# FmcConnector.net
KiCad netlist of a schematic drawn in Altium Designer
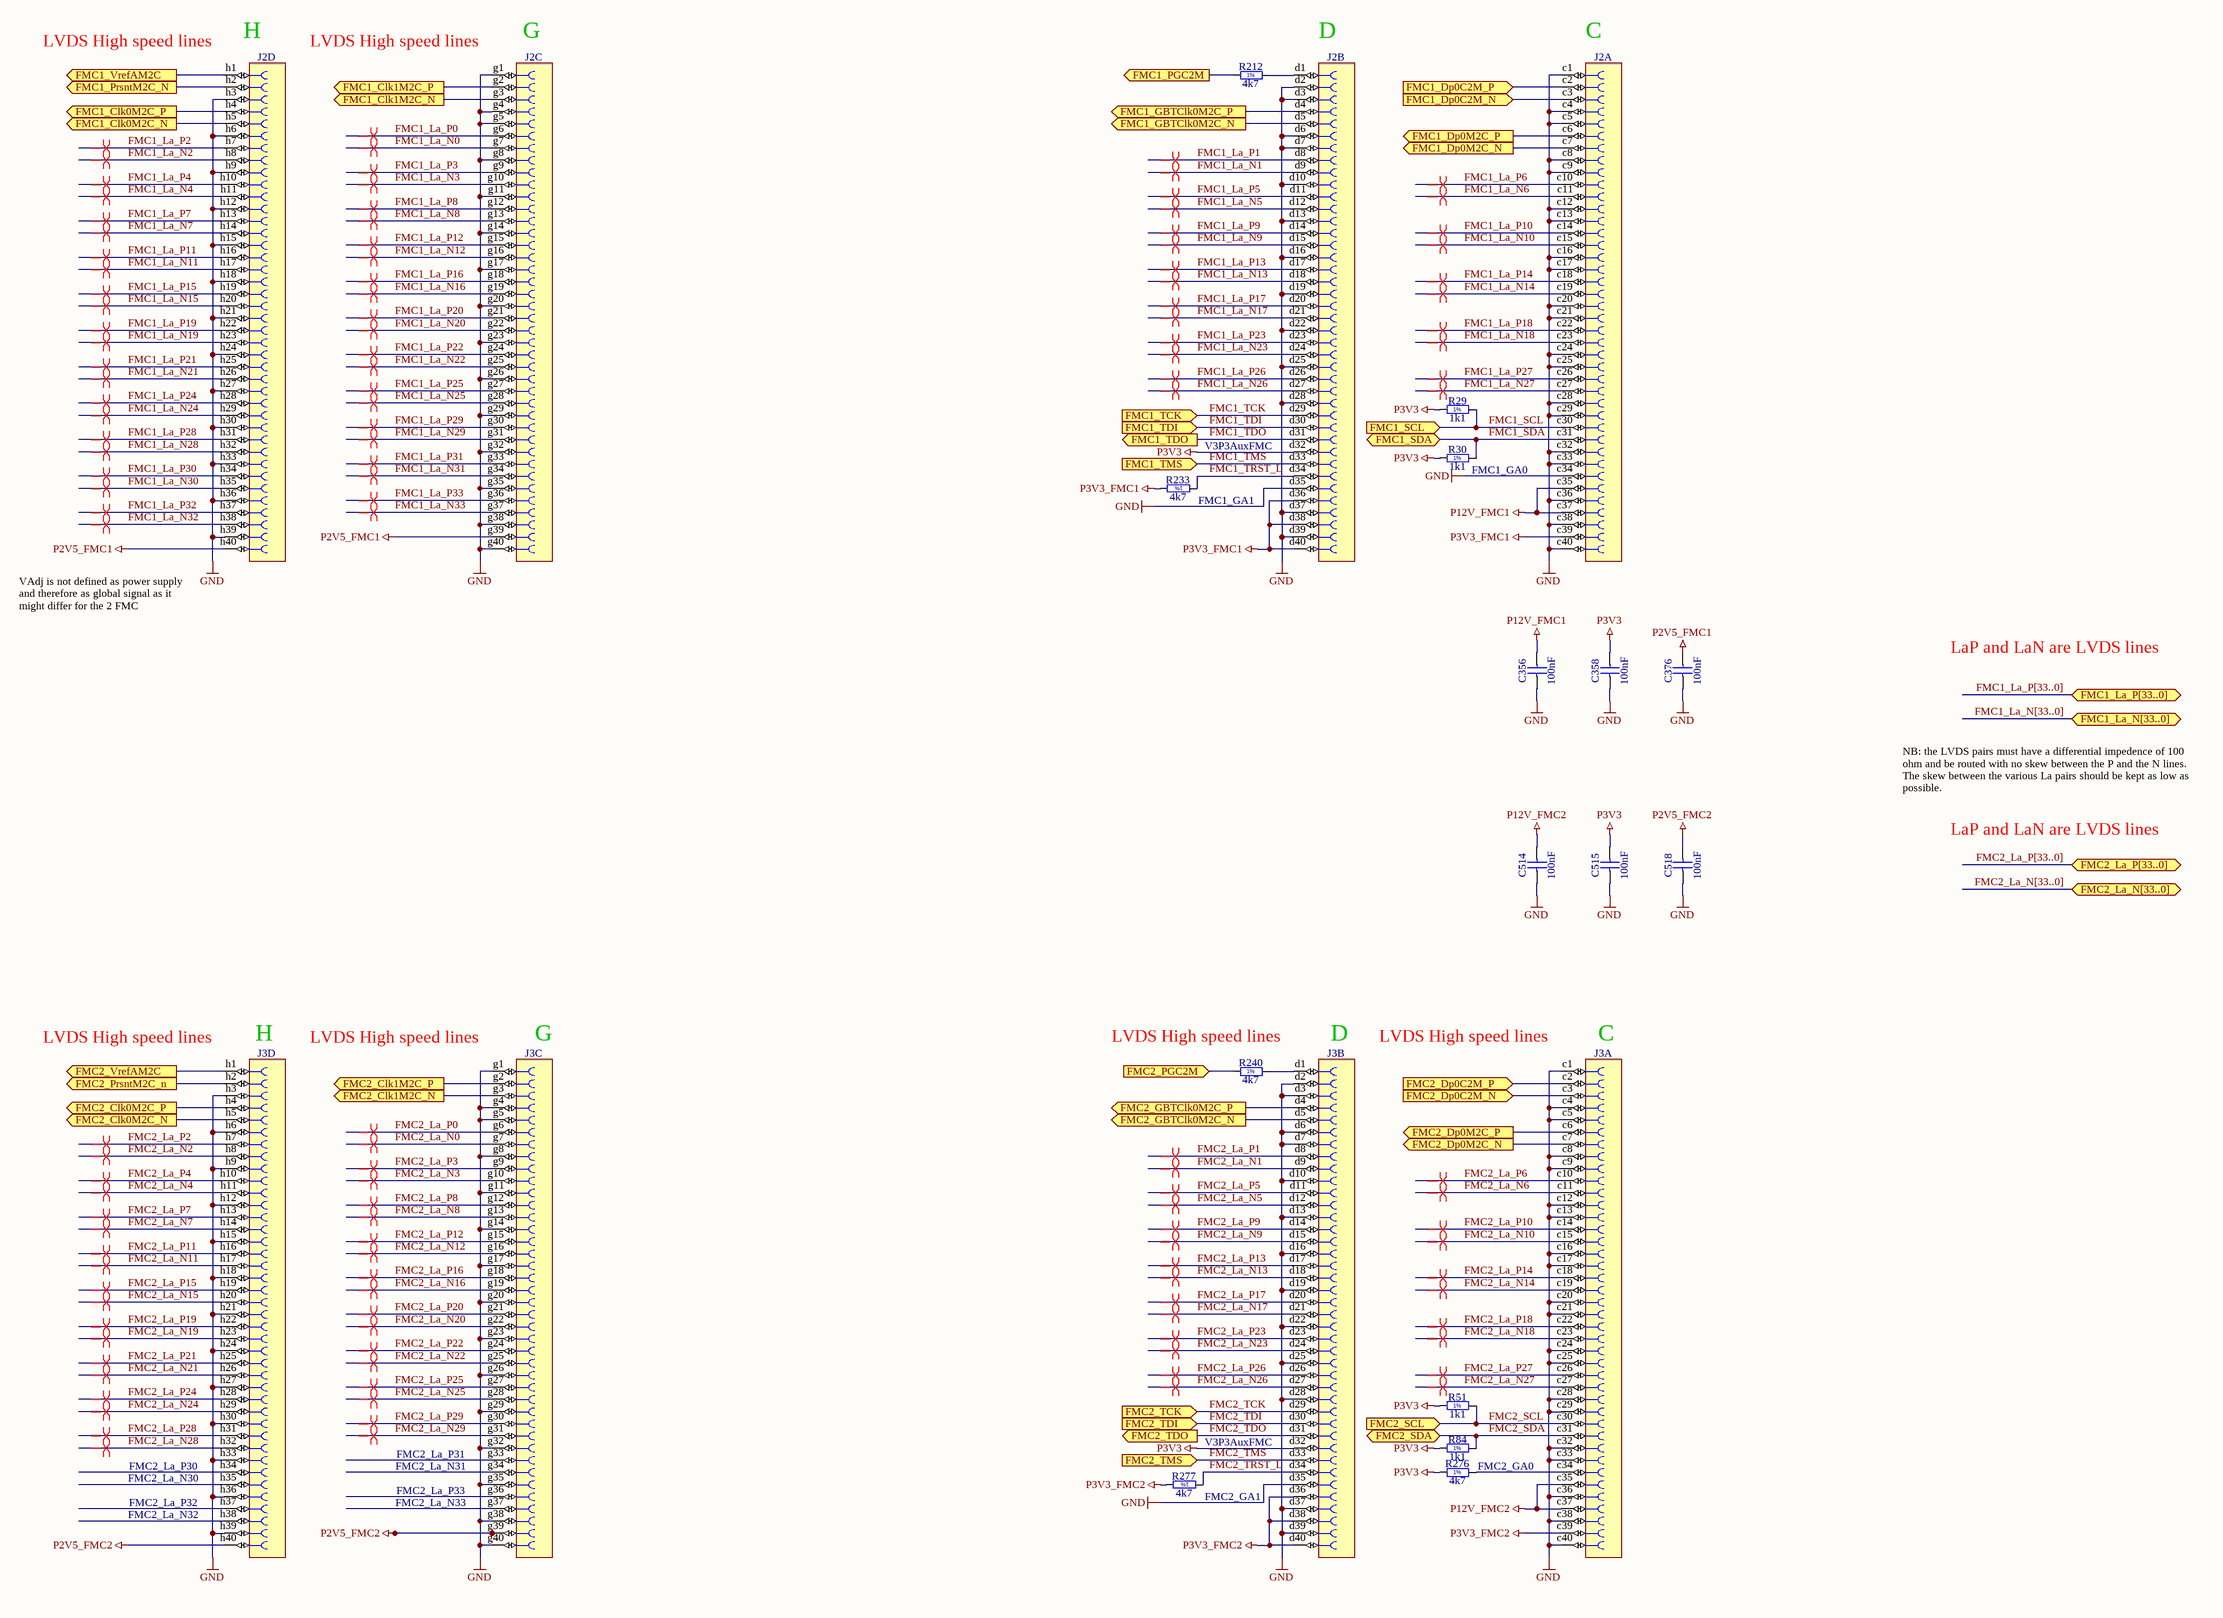
[diagram p0: FmcConnector.SchDoc]

(export (version "E")
  (design (tool "Eeschema 10.0.6"))
  (components
    (comp (ref "C356")
      (value "100nF")
      (footprint "CAPC1005X55N")
      (description "Non-polarised capacitor")
      (fields
        (field (name "PART NUMBER") "CC0402_100NF_16V_10%_X7R")
        (field (name "VOLTAGE") "16V")
        (field (name "AUTHOR") "CERN DEM JLC")
      )
      (libsource (lib "Capacitors") (part "Capacitor - non polarized"))
    )
    (comp (ref "C358")
      (value "100nF")
      (footprint "CAPC1005X55N")
      (description "Non-polarised capacitor")
      (fields
        (field (name "PART NUMBER") "CC0402_100NF_16V_10%_X7R")
        (field (name "VOLTAGE") "16V")
        (field (name "AUTHOR") "CERN DEM JLC")
      )
      (libsource (lib "Capacitors") (part "Capacitor - non polarized"))
    )
    (comp (ref "C376")
      (value "100nF")
      (footprint "CAPC1005X55N")
      (description "Non-polarised capacitor")
      (fields
        (field (name "PART NUMBER") "CC0402_100NF_16V_10%_X7R")
        (field (name "VOLTAGE") "16V")
        (field (name "AUTHOR") "CERN DEM JLC")
      )
      (libsource (lib "Capacitors") (part "Capacitor - non polarized"))
    )
    (comp (ref "C514")
      (value "100nF")
      (footprint "CAPC1005X55N")
      (description "Non-polarised capacitor")
      (fields
        (field (name "PART NUMBER") "CC0402_100NF_16V_10%_X7R")
        (field (name "VOLTAGE") "16V")
        (field (name "AUTHOR") "CERN DEM JLC")
      )
      (libsource (lib "Capacitors") (part "Capacitor - non polarized"))
    )
    (comp (ref "C515")
      (value "100nF")
      (footprint "CAPC1005X55N")
      (description "Non-polarised capacitor")
      (fields
        (field (name "PART NUMBER") "CC0402_100NF_16V_10%_X7R")
        (field (name "VOLTAGE") "16V")
        (field (name "AUTHOR") "CERN DEM JLC")
      )
      (libsource (lib "Capacitors") (part "Capacitor - non polarized"))
    )
    (comp (ref "C518")
      (value "100nF")
      (footprint "CAPC1005X55N")
      (description "Non-polarised capacitor")
      (fields
        (field (name "PART NUMBER") "CC0402_100NF_16V_10%_X7R")
        (field (name "VOLTAGE") "16V")
        (field (name "AUTHOR") "CERN DEM JLC")
      )
      (libsource (lib "Capacitors") (part "Capacitor - non polarized"))
    )
    (comp (ref "J2")
      (value "VITA 57")
      (footprint "SAMTEC_ASP-134603-01")
      (description "Connector VITA 57, 160 Female contacts in 4 row cdgh")
      (fields
        (field (name "PART NUMBER") "SAMTEC_ASP-134603-01")
        (field (name "MANUFACTURER") "SAMTEC")
        (field (name "AUTHOR") "CERN DEM JLC")
      )
      (libsource (lib "Connectors") (part "Connector VITA 57 160 Female (cdgh)"))
    )
    (comp (ref "J3")
      (value "VITA 57")
      (footprint "SAMTEC_ASP-134603-01")
      (description "Connector VITA 57, 160 Female contacts in 4 row cdgh")
      (fields
        (field (name "PART NUMBER") "SAMTEC_ASP-134603-01")
        (field (name "MANUFACTURER") "SAMTEC")
        (field (name "AUTHOR") "CERN DEM JLC")
      )
      (libsource (lib "Connectors") (part "Connector VITA 57 160 Female (cdgh)"))
    )
    (comp (ref "R29")
      (value "1k1")
      (footprint "RESC1608X55N")
      (description "Resistor - 1%")
      (fields
        (field (name "PART NUMBER") "R0603_1K1_1%_0.1W_100PPM")
        (field (name "POWER") "0.1W")
        (field (name "AUTHOR") "CERN DEM JLC")
      )
      (libsource (lib "Resistors") (part "Resistor - 1%"))
    )
    (comp (ref "R30")
      (value "1k1")
      (footprint "RESC1608X55N")
      (description "Resistor - 1%")
      (fields
        (field (name "PART NUMBER") "R0603_1K1_1%_0.1W_100PPM")
        (field (name "POWER") "0.1W")
        (field (name "AUTHOR") "CERN DEM JLC")
      )
      (libsource (lib "Resistors") (part "Resistor - 1%"))
    )
    (comp (ref "R51")
      (value "1k1")
      (footprint "RESC1608X55N")
      (description "Resistor - 1%")
      (fields
        (field (name "PART NUMBER") "R0603_1K1_1%_0.1W_100PPM")
        (field (name "POWER") "0.1W")
        (field (name "AUTHOR") "CERN DEM JLC")
      )
      (libsource (lib "Resistors") (part "Resistor - 1%"))
    )
    (comp (ref "R84")
      (value "1k1")
      (footprint "RESC1608X55N")
      (description "Resistor - 1%")
      (fields
        (field (name "PART NUMBER") "R0603_1K1_1%_0.1W_100PPM")
        (field (name "POWER") "0.1W")
        (field (name "AUTHOR") "CERN DEM JLC")
      )
      (libsource (lib "Resistors") (part "Resistor - 1%"))
    )
    (comp (ref "R212")
      (value "4k7")
      (footprint "RESC1608X55N")
      (description "Resistor - 1%")
      (fields
        (field (name "PART NUMBER") "R0603_4K7_1%_0.1W_100PPM")
        (field (name "POWER") "0.1W")
        (field (name "AUTHOR") "CERN DEM JLC")
      )
      (libsource (lib "Resistors") (part "Resistor - 1%"))
    )
    (comp (ref "R233")
      (value "4k7")
      (footprint "RESC1608X55N")
      (description "Resistor - 1%")
      (fields
        (field (name "PART NUMBER") "R0603_4K7_1%_0.1W_100PPM")
        (field (name "POWER") "0.1W")
        (field (name "AUTHOR") "CERN DEM JLC")
      )
      (libsource (lib "") (part "Resistor - 1%_1"))
    )
    (comp (ref "R240")
      (value "4k7")
      (footprint "RESC1608X55N")
      (description "Resistor - 1%")
      (fields
        (field (name "PART NUMBER") "R0603_4K7_1%_0.1W_100PPM")
        (field (name "POWER") "0.1W")
        (field (name "AUTHOR") "CERN DEM JLC")
      )
      (libsource (lib "Resistors") (part "Resistor - 1%"))
    )
    (comp (ref "R276")
      (value "4k7")
      (footprint "RESC1608X55N")
      (description "Resistor - 1%")
      (fields
        (field (name "PART NUMBER") "R0603_4K7_1%_0.1W_100PPM")
        (field (name "POWER") "0.1W")
        (field (name "AUTHOR") "CERN DEM JLC")
      )
      (libsource (lib "Resistors") (part "Resistor - 1%"))
    )
    (comp (ref "R277")
      (value "4k7")
      (footprint "RESC1608X55N")
      (description "Resistor - 1%")
      (fields
        (field (name "PART NUMBER") "R0603_4K7_1%_0.1W_100PPM")
        (field (name "POWER") "0.1W")
        (field (name "AUTHOR") "CERN DEM JLC")
      )
      (libsource (lib "") (part "Resistor - 1%_1"))
    )
  )
  (nets
    (net (code "9") (name "/FMC1_Clk0M2C_N") (class "Default")
      (node (ref "J2") (pin "h5") (pinfunction "h5_h5") (pintype "bidirectional"))
    )
    (net (code "10") (name "/FMC1_Clk0M2C_P") (class "Default")
      (node (ref "J2") (pin "h4") (pinfunction "h4_h4") (pintype "bidirectional"))
    )
    (net (code "11") (name "/FMC1_Clk1M2C_N") (class "Default")
      (node (ref "J2") (pin "g3") (pinfunction "g3_g3") (pintype "bidirectional"))
    )
    (net (code "12") (name "/FMC1_Clk1M2C_P") (class "Default")
      (node (ref "J2") (pin "g2") (pinfunction "g2_g2") (pintype "bidirectional"))
    )
    (net (code "13") (name "/FMC1_Dp0C2M_N") (class "Default")
      (node (ref "J2") (pin "c3") (pinfunction "c3_c3") (pintype "bidirectional"))
    )
    (net (code "14") (name "/FMC1_Dp0C2M_P") (class "Default")
      (node (ref "J2") (pin "c2") (pinfunction "c2_c2") (pintype "bidirectional"))
    )
    (net (code "15") (name "/FMC1_Dp0M2C_N") (class "Default")
      (node (ref "J2") (pin "c7") (pinfunction "c7_c7") (pintype "bidirectional"))
    )
    (net (code "16") (name "/FMC1_Dp0M2C_P") (class "Default")
      (node (ref "J2") (pin "c6") (pinfunction "c6_c6") (pintype "bidirectional"))
    )
    (net (code "17") (name "/FMC1_GBTClk0M2C_N") (class "Default")
      (node (ref "J2") (pin "d5") (pinfunction "d5_d5") (pintype "bidirectional"))
    )
    (net (code "18") (name "/FMC1_GBTClk0M2C_P") (class "Default")
      (node (ref "J2") (pin "d4") (pinfunction "d4_d4") (pintype "bidirectional"))
    )
    (net (code "19") (name "/FMC1_La_N0") (class "Default")
      (node (ref "J2") (pin "g7") (pinfunction "g7_g7") (pintype "bidirectional"))
    )
    (net (code "20") (name "/FMC1_La_N1") (class "Default")
      (node (ref "J2") (pin "d9") (pinfunction "d9_d9") (pintype "bidirectional"))
    )
    (net (code "21") (name "/FMC1_La_N2") (class "Default")
      (node (ref "J2") (pin "h8") (pinfunction "h8_h8") (pintype "bidirectional"))
    )
    (net (code "22") (name "/FMC1_La_N3") (class "Default")
      (node (ref "J2") (pin "g10") (pinfunction "g10_g10") (pintype "bidirectional"))
    )
    (net (code "23") (name "/FMC1_La_N4") (class "Default")
      (node (ref "J2") (pin "h11") (pinfunction "h11_h11") (pintype "bidirectional"))
    )
    (net (code "24") (name "/FMC1_La_N5") (class "Default")
      (node (ref "J2") (pin "d12") (pinfunction "d12_d12") (pintype "bidirectional"))
    )
    (net (code "25") (name "/FMC1_La_N6") (class "Default")
      (node (ref "J2") (pin "c11") (pinfunction "c11_c11") (pintype "bidirectional"))
    )
    (net (code "26") (name "/FMC1_La_N7") (class "Default")
      (node (ref "J2") (pin "h14") (pinfunction "h14_h14") (pintype "bidirectional"))
    )
    (net (code "27") (name "/FMC1_La_N8") (class "Default")
      (node (ref "J2") (pin "g13") (pinfunction "g13_g13") (pintype "bidirectional"))
    )
    (net (code "28") (name "/FMC1_La_N9") (class "Default")
      (node (ref "J2") (pin "d15") (pinfunction "d15_d15") (pintype "bidirectional"))
    )
    (net (code "29") (name "/FMC1_La_N10") (class "Default")
      (node (ref "J2") (pin "c15") (pinfunction "c15_c15") (pintype "bidirectional"))
    )
    (net (code "30") (name "/FMC1_La_N11") (class "Default")
      (node (ref "J2") (pin "h17") (pinfunction "h17_h17") (pintype "bidirectional"))
    )
    (net (code "31") (name "/FMC1_La_N12") (class "Default")
      (node (ref "J2") (pin "g16") (pinfunction "g16_g16") (pintype "bidirectional"))
    )
    (net (code "32") (name "/FMC1_La_N13") (class "Default")
      (node (ref "J2") (pin "d18") (pinfunction "d18_d18") (pintype "bidirectional"))
    )
    (net (code "33") (name "/FMC1_La_N14") (class "Default")
      (node (ref "J2") (pin "c19") (pinfunction "c19_c19") (pintype "bidirectional"))
    )
    (net (code "34") (name "/FMC1_La_N15") (class "Default")
      (node (ref "J2") (pin "h20") (pinfunction "h20_h20") (pintype "bidirectional"))
    )
    (net (code "35") (name "/FMC1_La_N16") (class "Default")
      (node (ref "J2") (pin "g19") (pinfunction "g19_g19") (pintype "bidirectional"))
    )
    (net (code "36") (name "/FMC1_La_N17") (class "Default")
      (node (ref "J2") (pin "d21") (pinfunction "d21_d21") (pintype "bidirectional"))
    )
    (net (code "37") (name "/FMC1_La_N18") (class "Default")
      (node (ref "J2") (pin "c23") (pinfunction "c23_c23") (pintype "bidirectional"))
    )
    (net (code "38") (name "/FMC1_La_N19") (class "Default")
      (node (ref "J2") (pin "h23") (pinfunction "h23_h23") (pintype "bidirectional"))
    )
    (net (code "39") (name "/FMC1_La_N20") (class "Default")
      (node (ref "J2") (pin "g22") (pinfunction "g22_g22") (pintype "bidirectional"))
    )
    (net (code "40") (name "/FMC1_La_N21") (class "Default")
      (node (ref "J2") (pin "h26") (pinfunction "h26_h26") (pintype "bidirectional"))
    )
    (net (code "41") (name "/FMC1_La_N22") (class "Default")
      (node (ref "J2") (pin "g25") (pinfunction "g25_g25") (pintype "bidirectional"))
    )
    (net (code "42") (name "/FMC1_La_N23") (class "Default")
      (node (ref "J2") (pin "d24") (pinfunction "d24_d24") (pintype "bidirectional"))
    )
    (net (code "43") (name "/FMC1_La_N24") (class "Default")
      (node (ref "J2") (pin "h29") (pinfunction "h29_h29") (pintype "bidirectional"))
    )
    (net (code "44") (name "/FMC1_La_N25") (class "Default")
      (node (ref "J2") (pin "g28") (pinfunction "g28_g28") (pintype "bidirectional"))
    )
    (net (code "45") (name "/FMC1_La_N26") (class "Default")
      (node (ref "J2") (pin "d27") (pinfunction "d27_d27") (pintype "bidirectional"))
    )
    (net (code "46") (name "/FMC1_La_N27") (class "Default")
      (node (ref "J2") (pin "c27") (pinfunction "c27_c27") (pintype "bidirectional"))
    )
    (net (code "47") (name "/FMC1_La_N28") (class "Default")
      (node (ref "J2") (pin "h32") (pinfunction "h32_h32") (pintype "bidirectional"))
    )
    (net (code "48") (name "/FMC1_La_N29") (class "Default")
      (node (ref "J2") (pin "g31") (pinfunction "g31_g31") (pintype "bidirectional"))
    )
    (net (code "49") (name "/FMC1_La_N30") (class "Default")
      (node (ref "J2") (pin "h35") (pinfunction "h35_h35") (pintype "bidirectional"))
    )
    (net (code "50") (name "/FMC1_La_N31") (class "Default")
      (node (ref "J2") (pin "g34") (pinfunction "g34_g34") (pintype "bidirectional"))
    )
    (net (code "51") (name "/FMC1_La_N32") (class "Default")
      (node (ref "J2") (pin "h38") (pinfunction "h38_h38") (pintype "bidirectional"))
    )
    (net (code "52") (name "/FMC1_La_N33") (class "Default")
      (node (ref "J2") (pin "g37") (pinfunction "g37_g37") (pintype "bidirectional"))
    )
    (net (code "54") (name "/FMC1_La_P0") (class "Default")
      (node (ref "J2") (pin "g6") (pinfunction "g6_g6") (pintype "bidirectional"))
    )
    (net (code "55") (name "/FMC1_La_P1") (class "Default")
      (node (ref "J2") (pin "d8") (pinfunction "d8_d8") (pintype "bidirectional"))
    )
    (net (code "56") (name "/FMC1_La_P2") (class "Default")
      (node (ref "J2") (pin "h7") (pinfunction "h7_h7") (pintype "bidirectional"))
    )
    (net (code "57") (name "/FMC1_La_P3") (class "Default")
      (node (ref "J2") (pin "g9") (pinfunction "g9_g9") (pintype "bidirectional"))
    )
    (net (code "58") (name "/FMC1_La_P4") (class "Default")
      (node (ref "J2") (pin "h10") (pinfunction "h10_h10") (pintype "bidirectional"))
    )
    (net (code "59") (name "/FMC1_La_P5") (class "Default")
      (node (ref "J2") (pin "d11") (pinfunction "d11_d11") (pintype "bidirectional"))
    )
    (net (code "60") (name "/FMC1_La_P6") (class "Default")
      (node (ref "J2") (pin "c10") (pinfunction "c10_c10") (pintype "bidirectional"))
    )
    (net (code "61") (name "/FMC1_La_P7") (class "Default")
      (node (ref "J2") (pin "h13") (pinfunction "h13_h13") (pintype "bidirectional"))
    )
    (net (code "62") (name "/FMC1_La_P8") (class "Default")
      (node (ref "J2") (pin "g12") (pinfunction "g12_g12") (pintype "bidirectional"))
    )
    (net (code "63") (name "/FMC1_La_P9") (class "Default")
      (node (ref "J2") (pin "d14") (pinfunction "d14_d14") (pintype "bidirectional"))
    )
    (net (code "64") (name "/FMC1_La_P10") (class "Default")
      (node (ref "J2") (pin "c14") (pinfunction "c14_c14") (pintype "bidirectional"))
    )
    (net (code "65") (name "/FMC1_La_P11") (class "Default")
      (node (ref "J2") (pin "h16") (pinfunction "h16_h16") (pintype "bidirectional"))
    )
    (net (code "66") (name "/FMC1_La_P12") (class "Default")
      (node (ref "J2") (pin "g15") (pinfunction "g15_g15") (pintype "bidirectional"))
    )
    (net (code "67") (name "/FMC1_La_P13") (class "Default")
      (node (ref "J2") (pin "d17") (pinfunction "d17_d17") (pintype "bidirectional"))
    )
    (net (code "68") (name "/FMC1_La_P14") (class "Default")
      (node (ref "J2") (pin "c18") (pinfunction "c18_c18") (pintype "bidirectional"))
    )
    (net (code "69") (name "/FMC1_La_P15") (class "Default")
      (node (ref "J2") (pin "h19") (pinfunction "h19_h19") (pintype "bidirectional"))
    )
    (net (code "70") (name "/FMC1_La_P16") (class "Default")
      (node (ref "J2") (pin "g18") (pinfunction "g18_g18") (pintype "bidirectional"))
    )
    (net (code "71") (name "/FMC1_La_P17") (class "Default")
      (node (ref "J2") (pin "d20") (pinfunction "d20_d20") (pintype "bidirectional"))
    )
    (net (code "72") (name "/FMC1_La_P18") (class "Default")
      (node (ref "J2") (pin "c22") (pinfunction "c22_c22") (pintype "bidirectional"))
    )
    (net (code "73") (name "/FMC1_La_P19") (class "Default")
      (node (ref "J2") (pin "h22") (pinfunction "h22_h22") (pintype "bidirectional"))
    )
    (net (code "74") (name "/FMC1_La_P20") (class "Default")
      (node (ref "J2") (pin "g21") (pinfunction "g21_g21") (pintype "bidirectional"))
    )
    (net (code "75") (name "/FMC1_La_P21") (class "Default")
      (node (ref "J2") (pin "h25") (pinfunction "h25_h25") (pintype "bidirectional"))
    )
    (net (code "76") (name "/FMC1_La_P22") (class "Default")
      (node (ref "J2") (pin "g24") (pinfunction "g24_g24") (pintype "bidirectional"))
    )
    (net (code "77") (name "/FMC1_La_P23") (class "Default")
      (node (ref "J2") (pin "d23") (pinfunction "d23_d23") (pintype "bidirectional"))
    )
    (net (code "78") (name "/FMC1_La_P24") (class "Default")
      (node (ref "J2") (pin "h28") (pinfunction "h28_h28") (pintype "bidirectional"))
    )
    (net (code "79") (name "/FMC1_La_P25") (class "Default")
      (node (ref "J2") (pin "g27") (pinfunction "g27_g27") (pintype "bidirectional"))
    )
    (net (code "80") (name "/FMC1_La_P26") (class "Default")
      (node (ref "J2") (pin "d26") (pinfunction "d26_d26") (pintype "bidirectional"))
    )
    (net (code "81") (name "/FMC1_La_P27") (class "Default")
      (node (ref "J2") (pin "c26") (pinfunction "c26_c26") (pintype "bidirectional"))
    )
    (net (code "82") (name "/FMC1_La_P28") (class "Default")
      (node (ref "J2") (pin "h31") (pinfunction "h31_h31") (pintype "bidirectional"))
    )
    (net (code "83") (name "/FMC1_La_P29") (class "Default")
      (node (ref "J2") (pin "g30") (pinfunction "g30_g30") (pintype "bidirectional"))
    )
    (net (code "84") (name "/FMC1_La_P30") (class "Default")
      (node (ref "J2") (pin "h34") (pinfunction "h34_h34") (pintype "bidirectional"))
    )
    (net (code "85") (name "/FMC1_La_P31") (class "Default")
      (node (ref "J2") (pin "g33") (pinfunction "g33_g33") (pintype "bidirectional"))
    )
    (net (code "86") (name "/FMC1_La_P32") (class "Default")
      (node (ref "J2") (pin "h37") (pinfunction "h37_h37") (pintype "bidirectional"))
    )
    (net (code "87") (name "/FMC1_La_P33") (class "Default")
      (node (ref "J2") (pin "g36") (pinfunction "g36_g36") (pintype "bidirectional"))
    )
    (net (code "89") (name "/FMC1_PGC2M") (class "Default")
      (node (ref "R212") (pin "1") (pinfunction "1_1") (pintype "passive"))
    )
    (net (code "90") (name "/FMC1_PrsntM2C_N") (class "Default")
      (node (ref "J2") (pin "h2") (pinfunction "h2_h2") (pintype "bidirectional"))
    )
    (net (code "91") (name "/FMC1_SCL") (class "Default")
      (node (ref "J2") (pin "c30") (pinfunction "c30_c30") (pintype "bidirectional"))
      (node (ref "R29") (pin "2") (pinfunction "2_2") (pintype "passive"))
    )
    (net (code "92") (name "/FMC1_SDA") (class "Default")
      (node (ref "J2") (pin "c31") (pinfunction "c31_c31") (pintype "bidirectional"))
      (node (ref "R30") (pin "2") (pinfunction "2_2") (pintype "passive"))
    )
    (net (code "93") (name "/FMC1_TCK") (class "Default")
      (node (ref "J2") (pin "d29") (pinfunction "d29_d29") (pintype "bidirectional"))
    )
    (net (code "94") (name "/FMC1_TDI") (class "Default")
      (node (ref "J2") (pin "d30") (pinfunction "d30_d30") (pintype "bidirectional"))
    )
    (net (code "95") (name "/FMC1_TDO") (class "Default")
      (node (ref "J2") (pin "d31") (pinfunction "d31_d31") (pintype "bidirectional"))
    )
    (net (code "96") (name "/FMC1_TMS") (class "Default")
      (node (ref "J2") (pin "d33") (pinfunction "d33_d33") (pintype "bidirectional"))
    )
    (net (code "97") (name "/FMC1_TRST_L") (class "Default")
      (node (ref "J2") (pin "d34") (pinfunction "d34_d34") (pintype "bidirectional"))
      (node (ref "R233") (pin "1") (pinfunction "1_1") (pintype "passive"))
    )
    (net (code "98") (name "/FMC1_VrefAM2C") (class "Default")
      (node (ref "J2") (pin "h1") (pinfunction "h1_h1") (pintype "bidirectional"))
    )
    (net (code "99") (name "/FMC2_Clk0M2C_N") (class "Default")
      (node (ref "J3") (pin "h5") (pinfunction "h5_h5") (pintype "bidirectional"))
    )
    (net (code "100") (name "/FMC2_Clk0M2C_P") (class "Default")
      (node (ref "J3") (pin "h4") (pinfunction "h4_h4") (pintype "bidirectional"))
    )
    (net (code "101") (name "/FMC2_Clk1M2C_N") (class "Default")
      (node (ref "J3") (pin "g3") (pinfunction "g3_g3") (pintype "bidirectional"))
    )
    (net (code "102") (name "/FMC2_Clk1M2C_P") (class "Default")
      (node (ref "J3") (pin "g2") (pinfunction "g2_g2") (pintype "bidirectional"))
    )
    (net (code "103") (name "/FMC2_Dp0C2M_N") (class "Default")
      (node (ref "J3") (pin "c3") (pinfunction "c3_c3") (pintype "bidirectional"))
    )
    (net (code "104") (name "/FMC2_Dp0C2M_P") (class "Default")
      (node (ref "J3") (pin "c2") (pinfunction "c2_c2") (pintype "bidirectional"))
    )
    (net (code "105") (name "/FMC2_Dp0M2C_N") (class "Default")
      (node (ref "J3") (pin "c7") (pinfunction "c7_c7") (pintype "bidirectional"))
    )
    (net (code "106") (name "/FMC2_Dp0M2C_P") (class "Default")
      (node (ref "J3") (pin "c6") (pinfunction "c6_c6") (pintype "bidirectional"))
    )
    (net (code "107") (name "/FMC2_GBTClk0M2C_N") (class "Default")
      (node (ref "J3") (pin "d5") (pinfunction "d5_d5") (pintype "bidirectional"))
    )
    (net (code "108") (name "/FMC2_GBTClk0M2C_P") (class "Default")
      (node (ref "J3") (pin "d4") (pinfunction "d4_d4") (pintype "bidirectional"))
    )
    (net (code "109") (name "/FMC2_La_N0") (class "Default")
      (node (ref "J3") (pin "g7") (pinfunction "g7_g7") (pintype "bidirectional"))
    )
    (net (code "110") (name "/FMC2_La_N1") (class "Default")
      (node (ref "J3") (pin "d9") (pinfunction "d9_d9") (pintype "bidirectional"))
    )
    (net (code "111") (name "/FMC2_La_N2") (class "Default")
      (node (ref "J3") (pin "h8") (pinfunction "h8_h8") (pintype "bidirectional"))
    )
    (net (code "112") (name "/FMC2_La_N3") (class "Default")
      (node (ref "J3") (pin "g10") (pinfunction "g10_g10") (pintype "bidirectional"))
    )
    (net (code "113") (name "/FMC2_La_N4") (class "Default")
      (node (ref "J3") (pin "h11") (pinfunction "h11_h11") (pintype "bidirectional"))
    )
    (net (code "114") (name "/FMC2_La_N5") (class "Default")
      (node (ref "J3") (pin "d12") (pinfunction "d12_d12") (pintype "bidirectional"))
    )
    (net (code "115") (name "/FMC2_La_N6") (class "Default")
      (node (ref "J3") (pin "c11") (pinfunction "c11_c11") (pintype "bidirectional"))
    )
    (net (code "116") (name "/FMC2_La_N7") (class "Default")
      (node (ref "J3") (pin "h14") (pinfunction "h14_h14") (pintype "bidirectional"))
    )
    (net (code "117") (name "/FMC2_La_N8") (class "Default")
      (node (ref "J3") (pin "g13") (pinfunction "g13_g13") (pintype "bidirectional"))
    )
    (net (code "118") (name "/FMC2_La_N9") (class "Default")
      (node (ref "J3") (pin "d15") (pinfunction "d15_d15") (pintype "bidirectional"))
    )
    (net (code "119") (name "/FMC2_La_N10") (class "Default")
      (node (ref "J3") (pin "c15") (pinfunction "c15_c15") (pintype "bidirectional"))
    )
    (net (code "120") (name "/FMC2_La_N11") (class "Default")
      (node (ref "J3") (pin "h17") (pinfunction "h17_h17") (pintype "bidirectional"))
    )
    (net (code "121") (name "/FMC2_La_N12") (class "Default")
      (node (ref "J3") (pin "g16") (pinfunction "g16_g16") (pintype "bidirectional"))
    )
    (net (code "122") (name "/FMC2_La_N13") (class "Default")
      (node (ref "J3") (pin "d18") (pinfunction "d18_d18") (pintype "bidirectional"))
    )
    (net (code "123") (name "/FMC2_La_N14") (class "Default")
      (node (ref "J3") (pin "c19") (pinfunction "c19_c19") (pintype "bidirectional"))
    )
    (net (code "124") (name "/FMC2_La_N15") (class "Default")
      (node (ref "J3") (pin "h20") (pinfunction "h20_h20") (pintype "bidirectional"))
    )
    (net (code "125") (name "/FMC2_La_N16") (class "Default")
      (node (ref "J3") (pin "g19") (pinfunction "g19_g19") (pintype "bidirectional"))
    )
    (net (code "126") (name "/FMC2_La_N17") (class "Default")
      (node (ref "J3") (pin "d21") (pinfunction "d21_d21") (pintype "bidirectional"))
    )
    (net (code "127") (name "/FMC2_La_N18") (class "Default")
      (node (ref "J3") (pin "c23") (pinfunction "c23_c23") (pintype "bidirectional"))
    )
    (net (code "128") (name "/FMC2_La_N19") (class "Default")
      (node (ref "J3") (pin "h23") (pinfunction "h23_h23") (pintype "bidirectional"))
    )
    (net (code "129") (name "/FMC2_La_N20") (class "Default")
      (node (ref "J3") (pin "g22") (pinfunction "g22_g22") (pintype "bidirectional"))
    )
    (net (code "130") (name "/FMC2_La_N21") (class "Default")
      (node (ref "J3") (pin "h26") (pinfunction "h26_h26") (pintype "bidirectional"))
    )
    (net (code "131") (name "/FMC2_La_N22") (class "Default")
      (node (ref "J3") (pin "g25") (pinfunction "g25_g25") (pintype "bidirectional"))
    )
    (net (code "132") (name "/FMC2_La_N23") (class "Default")
      (node (ref "J3") (pin "d24") (pinfunction "d24_d24") (pintype "bidirectional"))
    )
    (net (code "133") (name "/FMC2_La_N24") (class "Default")
      (node (ref "J3") (pin "h29") (pinfunction "h29_h29") (pintype "bidirectional"))
    )
    (net (code "134") (name "/FMC2_La_N25") (class "Default")
      (node (ref "J3") (pin "g28") (pinfunction "g28_g28") (pintype "bidirectional"))
    )
    (net (code "135") (name "/FMC2_La_N26") (class "Default")
      (node (ref "J3") (pin "d27") (pinfunction "d27_d27") (pintype "bidirectional"))
    )
    (net (code "136") (name "/FMC2_La_N27") (class "Default")
      (node (ref "J3") (pin "c27") (pinfunction "c27_c27") (pintype "bidirectional"))
    )
    (net (code "137") (name "/FMC2_La_N28") (class "Default")
      (node (ref "J3") (pin "h32") (pinfunction "h32_h32") (pintype "bidirectional"))
    )
    (net (code "138") (name "/FMC2_La_N29") (class "Default")
      (node (ref "J3") (pin "g31") (pinfunction "g31_g31") (pintype "bidirectional"))
    )
    (net (code "140") (name "/FMC2_La_P0") (class "Default")
      (node (ref "J3") (pin "g6") (pinfunction "g6_g6") (pintype "bidirectional"))
    )
    (net (code "141") (name "/FMC2_La_P1") (class "Default")
      (node (ref "J3") (pin "d8") (pinfunction "d8_d8") (pintype "bidirectional"))
    )
    (net (code "142") (name "/FMC2_La_P2") (class "Default")
      (node (ref "J3") (pin "h7") (pinfunction "h7_h7") (pintype "bidirectional"))
    )
    (net (code "143") (name "/FMC2_La_P3") (class "Default")
      (node (ref "J3") (pin "g9") (pinfunction "g9_g9") (pintype "bidirectional"))
    )
    (net (code "144") (name "/FMC2_La_P4") (class "Default")
      (node (ref "J3") (pin "h10") (pinfunction "h10_h10") (pintype "bidirectional"))
    )
    (net (code "145") (name "/FMC2_La_P5") (class "Default")
      (node (ref "J3") (pin "d11") (pinfunction "d11_d11") (pintype "bidirectional"))
    )
    (net (code "146") (name "/FMC2_La_P6") (class "Default")
      (node (ref "J3") (pin "c10") (pinfunction "c10_c10") (pintype "bidirectional"))
    )
    (net (code "147") (name "/FMC2_La_P7") (class "Default")
      (node (ref "J3") (pin "h13") (pinfunction "h13_h13") (pintype "bidirectional"))
    )
    (net (code "148") (name "/FMC2_La_P8") (class "Default")
      (node (ref "J3") (pin "g12") (pinfunction "g12_g12") (pintype "bidirectional"))
    )
    (net (code "149") (name "/FMC2_La_P9") (class "Default")
      (node (ref "J3") (pin "d14") (pinfunction "d14_d14") (pintype "bidirectional"))
    )
    (net (code "150") (name "/FMC2_La_P10") (class "Default")
      (node (ref "J3") (pin "c14") (pinfunction "c14_c14") (pintype "bidirectional"))
    )
    (net (code "151") (name "/FMC2_La_P11") (class "Default")
      (node (ref "J3") (pin "h16") (pinfunction "h16_h16") (pintype "bidirectional"))
    )
    (net (code "152") (name "/FMC2_La_P12") (class "Default")
      (node (ref "J3") (pin "g15") (pinfunction "g15_g15") (pintype "bidirectional"))
    )
    (net (code "153") (name "/FMC2_La_P13") (class "Default")
      (node (ref "J3") (pin "d17") (pinfunction "d17_d17") (pintype "bidirectional"))
    )
    (net (code "154") (name "/FMC2_La_P14") (class "Default")
      (node (ref "J3") (pin "c18") (pinfunction "c18_c18") (pintype "bidirectional"))
    )
    (net (code "155") (name "/FMC2_La_P15") (class "Default")
      (node (ref "J3") (pin "h19") (pinfunction "h19_h19") (pintype "bidirectional"))
    )
    (net (code "156") (name "/FMC2_La_P16") (class "Default")
      (node (ref "J3") (pin "g18") (pinfunction "g18_g18") (pintype "bidirectional"))
    )
    (net (code "157") (name "/FMC2_La_P17") (class "Default")
      (node (ref "J3") (pin "d20") (pinfunction "d20_d20") (pintype "bidirectional"))
    )
    (net (code "158") (name "/FMC2_La_P18") (class "Default")
      (node (ref "J3") (pin "c22") (pinfunction "c22_c22") (pintype "bidirectional"))
    )
    (net (code "159") (name "/FMC2_La_P19") (class "Default")
      (node (ref "J3") (pin "h22") (pinfunction "h22_h22") (pintype "bidirectional"))
    )
    (net (code "160") (name "/FMC2_La_P20") (class "Default")
      (node (ref "J3") (pin "g21") (pinfunction "g21_g21") (pintype "bidirectional"))
    )
    (net (code "161") (name "/FMC2_La_P21") (class "Default")
      (node (ref "J3") (pin "h25") (pinfunction "h25_h25") (pintype "bidirectional"))
    )
    (net (code "162") (name "/FMC2_La_P22") (class "Default")
      (node (ref "J3") (pin "g24") (pinfunction "g24_g24") (pintype "bidirectional"))
    )
    (net (code "163") (name "/FMC2_La_P23") (class "Default")
      (node (ref "J3") (pin "d23") (pinfunction "d23_d23") (pintype "bidirectional"))
    )
    (net (code "164") (name "/FMC2_La_P24") (class "Default")
      (node (ref "J3") (pin "h28") (pinfunction "h28_h28") (pintype "bidirectional"))
    )
    (net (code "165") (name "/FMC2_La_P25") (class "Default")
      (node (ref "J3") (pin "g27") (pinfunction "g27_g27") (pintype "bidirectional"))
    )
    (net (code "166") (name "/FMC2_La_P26") (class "Default")
      (node (ref "J3") (pin "d26") (pinfunction "d26_d26") (pintype "bidirectional"))
    )
    (net (code "167") (name "/FMC2_La_P27") (class "Default")
      (node (ref "J3") (pin "c26") (pinfunction "c26_c26") (pintype "bidirectional"))
    )
    (net (code "168") (name "/FMC2_La_P28") (class "Default")
      (node (ref "J3") (pin "h31") (pinfunction "h31_h31") (pintype "bidirectional"))
    )
    (net (code "169") (name "/FMC2_La_P29") (class "Default")
      (node (ref "J3") (pin "g30") (pinfunction "g30_g30") (pintype "bidirectional"))
    )
    (net (code "171") (name "/FMC2_PGC2M") (class "Default")
      (node (ref "R240") (pin "1") (pinfunction "1_1") (pintype "passive"))
    )
    (net (code "172") (name "/FMC2_PrsntM2C_n") (class "Default")
      (node (ref "J3") (pin "h2") (pinfunction "h2_h2") (pintype "bidirectional"))
    )
    (net (code "173") (name "/FMC2_SCL") (class "Default")
      (node (ref "J3") (pin "c30") (pinfunction "c30_c30") (pintype "bidirectional"))
      (node (ref "R51") (pin "2") (pinfunction "2_2") (pintype "passive"))
    )
    (net (code "174") (name "/FMC2_SDA") (class "Default")
      (node (ref "J3") (pin "c31") (pinfunction "c31_c31") (pintype "bidirectional"))
      (node (ref "R84") (pin "2") (pinfunction "2_2") (pintype "passive"))
    )
    (net (code "175") (name "/FMC2_TCK") (class "Default")
      (node (ref "J3") (pin "d29") (pinfunction "d29_d29") (pintype "bidirectional"))
    )
    (net (code "176") (name "/FMC2_TDI") (class "Default")
      (node (ref "J3") (pin "d30") (pinfunction "d30_d30") (pintype "bidirectional"))
    )
    (net (code "177") (name "/FMC2_TDO") (class "Default")
      (node (ref "J3") (pin "d31") (pinfunction "d31_d31") (pintype "bidirectional"))
    )
    (net (code "178") (name "/FMC2_TMS") (class "Default")
      (node (ref "J3") (pin "d33") (pinfunction "d33_d33") (pintype "bidirectional"))
    )
    (net (code "179") (name "/FMC2_TRST_L") (class "Default")
      (node (ref "J3") (pin "d34") (pinfunction "d34_d34") (pintype "bidirectional"))
      (node (ref "R277") (pin "1") (pinfunction "1_1") (pintype "passive"))
    )
    (net (code "180") (name "/FMC2_VrefAM2C") (class "Default")
      (node (ref "J3") (pin "h1") (pinfunction "h1_h1") (pintype "bidirectional"))
    )
    (net (code "181") (name "GND") (class "Default")
      (node (ref "C356") (pin "2") (pinfunction "2_2") (pintype "passive"))
      (node (ref "C358") (pin "2") (pinfunction "2_2") (pintype "passive"))
      (node (ref "C376") (pin "2") (pinfunction "2_2") (pintype "passive"))
      (node (ref "C514") (pin "2") (pinfunction "2_2") (pintype "passive"))
      (node (ref "C515") (pin "2") (pinfunction "2_2") (pintype "passive"))
      (node (ref "C518") (pin "2") (pinfunction "2_2") (pintype "passive"))
      (node (ref "J2") (pin "c1") (pinfunction "c1_c1") (pintype "bidirectional"))
      (node (ref "J2") (pin "c12") (pinfunction "c12_c12") (pintype "bidirectional"))
      (node (ref "J2") (pin "c13") (pinfunction "c13_c13") (pintype "bidirectional"))
      (node (ref "J2") (pin "c16") (pinfunction "c16_c16") (pintype "bidirectional"))
      (node (ref "J2") (pin "c17") (pinfunction "c17_c17") (pintype "bidirectional"))
      (node (ref "J2") (pin "c20") (pinfunction "c20_c20") (pintype "bidirectional"))
      (node (ref "J2") (pin "c21") (pinfunction "c21_c21") (pintype "bidirectional"))
      (node (ref "J2") (pin "c24") (pinfunction "c24_c24") (pintype "bidirectional"))
      (node (ref "J2") (pin "c25") (pinfunction "c25_c25") (pintype "bidirectional"))
      (node (ref "J2") (pin "c28") (pinfunction "c28_c28") (pintype "bidirectional"))
      (node (ref "J2") (pin "c29") (pinfunction "c29_c29") (pintype "bidirectional"))
      (node (ref "J2") (pin "c32") (pinfunction "c32_c32") (pintype "bidirectional"))
      (node (ref "J2") (pin "c33") (pinfunction "c33_c33") (pintype "bidirectional"))
      (node (ref "J2") (pin "c34") (pinfunction "c34_c34") (pintype "bidirectional"))
      (node (ref "J2") (pin "c36") (pinfunction "c36_c36") (pintype "bidirectional"))
      (node (ref "J2") (pin "c38") (pinfunction "c38_c38") (pintype "bidirectional"))
      (node (ref "J2") (pin "c4") (pinfunction "c4_c4") (pintype "bidirectional"))
      (node (ref "J2") (pin "c40") (pinfunction "c40_c40") (pintype "bidirectional"))
      (node (ref "J2") (pin "c5") (pinfunction "c5_c5") (pintype "bidirectional"))
      (node (ref "J2") (pin "c8") (pinfunction "c8_c8") (pintype "bidirectional"))
      (node (ref "J2") (pin "c9") (pinfunction "c9_c9") (pintype "bidirectional"))
      (node (ref "J2") (pin "d10") (pinfunction "d10_d10") (pintype "bidirectional"))
      (node (ref "J2") (pin "d13") (pinfunction "d13_d13") (pintype "bidirectional"))
      (node (ref "J2") (pin "d16") (pinfunction "d16_d16") (pintype "bidirectional"))
      (node (ref "J2") (pin "d19") (pinfunction "d19_d19") (pintype "bidirectional"))
      (node (ref "J2") (pin "d2") (pinfunction "d2_d2") (pintype "bidirectional"))
      (node (ref "J2") (pin "d22") (pinfunction "d22_d22") (pintype "bidirectional"))
      (node (ref "J2") (pin "d25") (pinfunction "d25_d25") (pintype "bidirectional"))
      (node (ref "J2") (pin "d28") (pinfunction "d28_d28") (pintype "bidirectional"))
      (node (ref "J2") (pin "d3") (pinfunction "d3_d3") (pintype "bidirectional"))
      (node (ref "J2") (pin "d35") (pinfunction "d35_d35") (pintype "bidirectional"))
      (node (ref "J2") (pin "d37") (pinfunction "d37_d37") (pintype "bidirectional"))
      (node (ref "J2") (pin "d39") (pinfunction "d39_d39") (pintype "bidirectional"))
      (node (ref "J2") (pin "d6") (pinfunction "d6_d6") (pintype "bidirectional"))
      (node (ref "J2") (pin "d7") (pinfunction "d7_d7") (pintype "bidirectional"))
      (node (ref "J2") (pin "g1") (pinfunction "g1_g1") (pintype "bidirectional"))
      (node (ref "J2") (pin "g11") (pinfunction "g11_g11") (pintype "bidirectional"))
      (node (ref "J2") (pin "g14") (pinfunction "g14_g14") (pintype "bidirectional"))
      (node (ref "J2") (pin "g17") (pinfunction "g17_g17") (pintype "bidirectional"))
      (node (ref "J2") (pin "g20") (pinfunction "g20_g20") (pintype "bidirectional"))
      (node (ref "J2") (pin "g23") (pinfunction "g23_g23") (pintype "bidirectional"))
      (node (ref "J2") (pin "g26") (pinfunction "g26_g26") (pintype "bidirectional"))
      (node (ref "J2") (pin "g29") (pinfunction "g29_g29") (pintype "bidirectional"))
      (node (ref "J2") (pin "g32") (pinfunction "g32_g32") (pintype "bidirectional"))
      (node (ref "J2") (pin "g35") (pinfunction "g35_g35") (pintype "bidirectional"))
      (node (ref "J2") (pin "g38") (pinfunction "g38_g38") (pintype "bidirectional"))
      (node (ref "J2") (pin "g4") (pinfunction "g4_g4") (pintype "bidirectional"))
      (node (ref "J2") (pin "g40") (pinfunction "g40_g40") (pintype "bidirectional"))
      (node (ref "J2") (pin "g5") (pinfunction "g5_g5") (pintype "bidirectional"))
      (node (ref "J2") (pin "g8") (pinfunction "g8_g8") (pintype "bidirectional"))
      (node (ref "J2") (pin "h12") (pinfunction "h12_h12") (pintype "bidirectional"))
      (node (ref "J2") (pin "h15") (pinfunction "h15_h15") (pintype "bidirectional"))
      (node (ref "J2") (pin "h18") (pinfunction "h18_h18") (pintype "bidirectional"))
      (node (ref "J2") (pin "h21") (pinfunction "h21_h21") (pintype "bidirectional"))
      (node (ref "J2") (pin "h24") (pinfunction "h24_h24") (pintype "bidirectional"))
      (node (ref "J2") (pin "h27") (pinfunction "h27_h27") (pintype "bidirectional"))
      (node (ref "J2") (pin "h3") (pinfunction "h3_h3") (pintype "bidirectional"))
      (node (ref "J2") (pin "h30") (pinfunction "h30_h30") (pintype "bidirectional"))
      (node (ref "J2") (pin "h33") (pinfunction "h33_h33") (pintype "bidirectional"))
      (node (ref "J2") (pin "h36") (pinfunction "h36_h36") (pintype "bidirectional"))
      (node (ref "J2") (pin "h39") (pinfunction "h39_h39") (pintype "bidirectional"))
      (node (ref "J2") (pin "h6") (pinfunction "h6_h6") (pintype "bidirectional"))
      (node (ref "J2") (pin "h9") (pinfunction "h9_h9") (pintype "bidirectional"))
      (node (ref "J3") (pin "c1") (pinfunction "c1_c1") (pintype "bidirectional"))
      (node (ref "J3") (pin "c12") (pinfunction "c12_c12") (pintype "bidirectional"))
      (node (ref "J3") (pin "c13") (pinfunction "c13_c13") (pintype "bidirectional"))
      (node (ref "J3") (pin "c16") (pinfunction "c16_c16") (pintype "bidirectional"))
      (node (ref "J3") (pin "c17") (pinfunction "c17_c17") (pintype "bidirectional"))
      (node (ref "J3") (pin "c20") (pinfunction "c20_c20") (pintype "bidirectional"))
      (node (ref "J3") (pin "c21") (pinfunction "c21_c21") (pintype "bidirectional"))
      (node (ref "J3") (pin "c24") (pinfunction "c24_c24") (pintype "bidirectional"))
      (node (ref "J3") (pin "c25") (pinfunction "c25_c25") (pintype "bidirectional"))
      (node (ref "J3") (pin "c28") (pinfunction "c28_c28") (pintype "bidirectional"))
      (node (ref "J3") (pin "c29") (pinfunction "c29_c29") (pintype "bidirectional"))
      (node (ref "J3") (pin "c32") (pinfunction "c32_c32") (pintype "bidirectional"))
      (node (ref "J3") (pin "c33") (pinfunction "c33_c33") (pintype "bidirectional"))
      (node (ref "J3") (pin "c36") (pinfunction "c36_c36") (pintype "bidirectional"))
      (node (ref "J3") (pin "c38") (pinfunction "c38_c38") (pintype "bidirectional"))
      (node (ref "J3") (pin "c4") (pinfunction "c4_c4") (pintype "bidirectional"))
      (node (ref "J3") (pin "c40") (pinfunction "c40_c40") (pintype "bidirectional"))
      (node (ref "J3") (pin "c5") (pinfunction "c5_c5") (pintype "bidirectional"))
      (node (ref "J3") (pin "c8") (pinfunction "c8_c8") (pintype "bidirectional"))
      (node (ref "J3") (pin "c9") (pinfunction "c9_c9") (pintype "bidirectional"))
      (node (ref "J3") (pin "d10") (pinfunction "d10_d10") (pintype "bidirectional"))
      (node (ref "J3") (pin "d13") (pinfunction "d13_d13") (pintype "bidirectional"))
      (node (ref "J3") (pin "d16") (pinfunction "d16_d16") (pintype "bidirectional"))
      (node (ref "J3") (pin "d19") (pinfunction "d19_d19") (pintype "bidirectional"))
      (node (ref "J3") (pin "d2") (pinfunction "d2_d2") (pintype "bidirectional"))
      (node (ref "J3") (pin "d22") (pinfunction "d22_d22") (pintype "bidirectional"))
      (node (ref "J3") (pin "d25") (pinfunction "d25_d25") (pintype "bidirectional"))
      (node (ref "J3") (pin "d28") (pinfunction "d28_d28") (pintype "bidirectional"))
      (node (ref "J3") (pin "d3") (pinfunction "d3_d3") (pintype "bidirectional"))
      (node (ref "J3") (pin "d35") (pinfunction "d35_d35") (pintype "bidirectional"))
      (node (ref "J3") (pin "d37") (pinfunction "d37_d37") (pintype "bidirectional"))
      (node (ref "J3") (pin "d39") (pinfunction "d39_d39") (pintype "bidirectional"))
      (node (ref "J3") (pin "d6") (pinfunction "d6_d6") (pintype "bidirectional"))
      (node (ref "J3") (pin "d7") (pinfunction "d7_d7") (pintype "bidirectional"))
      (node (ref "J3") (pin "g1") (pinfunction "g1_g1") (pintype "bidirectional"))
      (node (ref "J3") (pin "g11") (pinfunction "g11_g11") (pintype "bidirectional"))
      (node (ref "J3") (pin "g14") (pinfunction "g14_g14") (pintype "bidirectional"))
      (node (ref "J3") (pin "g17") (pinfunction "g17_g17") (pintype "bidirectional"))
      (node (ref "J3") (pin "g20") (pinfunction "g20_g20") (pintype "bidirectional"))
      (node (ref "J3") (pin "g23") (pinfunction "g23_g23") (pintype "bidirectional"))
      (node (ref "J3") (pin "g26") (pinfunction "g26_g26") (pintype "bidirectional"))
      (node (ref "J3") (pin "g29") (pinfunction "g29_g29") (pintype "bidirectional"))
      (node (ref "J3") (pin "g32") (pinfunction "g32_g32") (pintype "bidirectional"))
      (node (ref "J3") (pin "g35") (pinfunction "g35_g35") (pintype "bidirectional"))
      (node (ref "J3") (pin "g38") (pinfunction "g38_g38") (pintype "bidirectional"))
      (node (ref "J3") (pin "g4") (pinfunction "g4_g4") (pintype "bidirectional"))
      (node (ref "J3") (pin "g40") (pinfunction "g40_g40") (pintype "bidirectional"))
      (node (ref "J3") (pin "g5") (pinfunction "g5_g5") (pintype "bidirectional"))
      (node (ref "J3") (pin "g8") (pinfunction "g8_g8") (pintype "bidirectional"))
      (node (ref "J3") (pin "h12") (pinfunction "h12_h12") (pintype "bidirectional"))
      (node (ref "J3") (pin "h15") (pinfunction "h15_h15") (pintype "bidirectional"))
      (node (ref "J3") (pin "h18") (pinfunction "h18_h18") (pintype "bidirectional"))
      (node (ref "J3") (pin "h21") (pinfunction "h21_h21") (pintype "bidirectional"))
      (node (ref "J3") (pin "h24") (pinfunction "h24_h24") (pintype "bidirectional"))
      (node (ref "J3") (pin "h27") (pinfunction "h27_h27") (pintype "bidirectional"))
      (node (ref "J3") (pin "h3") (pinfunction "h3_h3") (pintype "bidirectional"))
      (node (ref "J3") (pin "h30") (pinfunction "h30_h30") (pintype "bidirectional"))
      (node (ref "J3") (pin "h33") (pinfunction "h33_h33") (pintype "bidirectional"))
      (node (ref "J3") (pin "h36") (pinfunction "h36_h36") (pintype "bidirectional"))
      (node (ref "J3") (pin "h39") (pinfunction "h39_h39") (pintype "bidirectional"))
      (node (ref "J3") (pin "h6") (pinfunction "h6_h6") (pintype "bidirectional"))
      (node (ref "J3") (pin "h9") (pinfunction "h9_h9") (pintype "bidirectional"))
    )
    (net (code "182") (name "Net-(J2-Padd1)") (class "Default")
      (node (ref "J2") (pin "d1") (pinfunction "d1_d1") (pintype "bidirectional"))
      (node (ref "R212") (pin "2") (pinfunction "2_2") (pintype "passive"))
    )
    (net (code "183") (name "Net-(J3-Padc34)") (class "Default")
      (node (ref "J3") (pin "c34") (pinfunction "c34_c34") (pintype "bidirectional"))
      (node (ref "R276") (pin "2") (pinfunction "2_2") (pintype "passive"))
    )
    (net (code "184") (name "Net-(J3-Padd1)") (class "Default")
      (node (ref "J3") (pin "d1") (pinfunction "d1_d1") (pintype "bidirectional"))
      (node (ref "R240") (pin "2") (pinfunction "2_2") (pintype "passive"))
    )
    (net (code "185") (name "P2V5_FMC1") (class "Default")
      (node (ref "C376") (pin "1") (pinfunction "1_1") (pintype "passive"))
      (node (ref "J2") (pin "g39") (pinfunction "g39_g39") (pintype "bidirectional"))
      (node (ref "J2") (pin "h40") (pinfunction "h40_h40") (pintype "bidirectional"))
    )
    (net (code "186") (name "P2V5_FMC2") (class "Default")
      (node (ref "C518") (pin "1") (pinfunction "1_1") (pintype "passive"))
      (node (ref "J3") (pin "g39") (pinfunction "g39_g39") (pintype "bidirectional"))
      (node (ref "J3") (pin "h40") (pinfunction "h40_h40") (pintype "bidirectional"))
    )
    (net (code "187") (name "P3V3") (class "Default")
      (node (ref "C358") (pin "1") (pinfunction "1_1") (pintype "passive"))
      (node (ref "C515") (pin "1") (pinfunction "1_1") (pintype "passive"))
      (node (ref "J2") (pin "d32") (pinfunction "d32_d32") (pintype "bidirectional"))
      (node (ref "J3") (pin "d32") (pinfunction "d32_d32") (pintype "bidirectional"))
      (node (ref "R276") (pin "1") (pinfunction "1_1") (pintype "passive"))
      (node (ref "R29") (pin "1") (pinfunction "1_1") (pintype "passive"))
      (node (ref "R30") (pin "1") (pinfunction "1_1") (pintype "passive"))
      (node (ref "R51") (pin "1") (pinfunction "1_1") (pintype "passive"))
      (node (ref "R84") (pin "1") (pinfunction "1_1") (pintype "passive"))
    )
    (net (code "188") (name "P3V3_FMC1") (class "Default")
      (node (ref "J2") (pin "c39") (pinfunction "c39_c39") (pintype "bidirectional"))
      (node (ref "J2") (pin "d36") (pinfunction "d36_d36") (pintype "bidirectional"))
      (node (ref "J2") (pin "d38") (pinfunction "d38_d38") (pintype "bidirectional"))
      (node (ref "J2") (pin "d40") (pinfunction "d40_d40") (pintype "bidirectional"))
      (node (ref "R233") (pin "2") (pinfunction "2_2") (pintype "passive"))
    )
    (net (code "189") (name "P3V3_FMC2") (class "Default")
      (node (ref "J3") (pin "c39") (pinfunction "c39_c39") (pintype "bidirectional"))
      (node (ref "J3") (pin "d36") (pinfunction "d36_d36") (pintype "bidirectional"))
      (node (ref "J3") (pin "d38") (pinfunction "d38_d38") (pintype "bidirectional"))
      (node (ref "J3") (pin "d40") (pinfunction "d40_d40") (pintype "bidirectional"))
      (node (ref "R277") (pin "2") (pinfunction "2_2") (pintype "passive"))
    )
    (net (code "190") (name "P12V_FMC1") (class "Default")
      (node (ref "C356") (pin "1") (pinfunction "1_1") (pintype "passive"))
      (node (ref "J2") (pin "c35") (pinfunction "c35_c35") (pintype "bidirectional"))
      (node (ref "J2") (pin "c37") (pinfunction "c37_c37") (pintype "bidirectional"))
    )
    (net (code "191") (name "P12V_FMC2") (class "Default")
      (node (ref "C514") (pin "1") (pinfunction "1_1") (pintype "passive"))
      (node (ref "J3") (pin "c35") (pinfunction "c35_c35") (pintype "bidirectional"))
      (node (ref "J3") (pin "c37") (pinfunction "c37_c37") (pintype "bidirectional"))
    )
    (net (code "192") (name "unconnected-(J3-Padg33)") (class "Default")
      (node (ref "J3") (pin "g33") (pinfunction "g33_g33") (pintype "bidirectional"))
    )
    (net (code "193") (name "unconnected-(J3-Padg34)") (class "Default")
      (node (ref "J3") (pin "g34") (pinfunction "g34_g34") (pintype "bidirectional"))
    )
    (net (code "194") (name "unconnected-(J3-Padg36)") (class "Default")
      (node (ref "J3") (pin "g36") (pinfunction "g36_g36") (pintype "bidirectional"))
    )
    (net (code "195") (name "unconnected-(J3-Padg37)") (class "Default")
      (node (ref "J3") (pin "g37") (pinfunction "g37_g37") (pintype "bidirectional"))
    )
    (net (code "196") (name "unconnected-(J3-Padh34)") (class "Default")
      (node (ref "J3") (pin "h34") (pinfunction "h34_h34") (pintype "bidirectional"))
    )
    (net (code "197") (name "unconnected-(J3-Padh35)") (class "Default")
      (node (ref "J3") (pin "h35") (pinfunction "h35_h35") (pintype "bidirectional"))
    )
    (net (code "198") (name "unconnected-(J3-Padh37)") (class "Default")
      (node (ref "J3") (pin "h37") (pinfunction "h37_h37") (pintype "bidirectional"))
    )
    (net (code "199") (name "unconnected-(J3-Padh38)") (class "Default")
      (node (ref "J3") (pin "h38") (pinfunction "h38_h38") (pintype "bidirectional"))
    )
  )
)
